# adc.net
KiCad netlist of a schematic drawn in Altium Designer
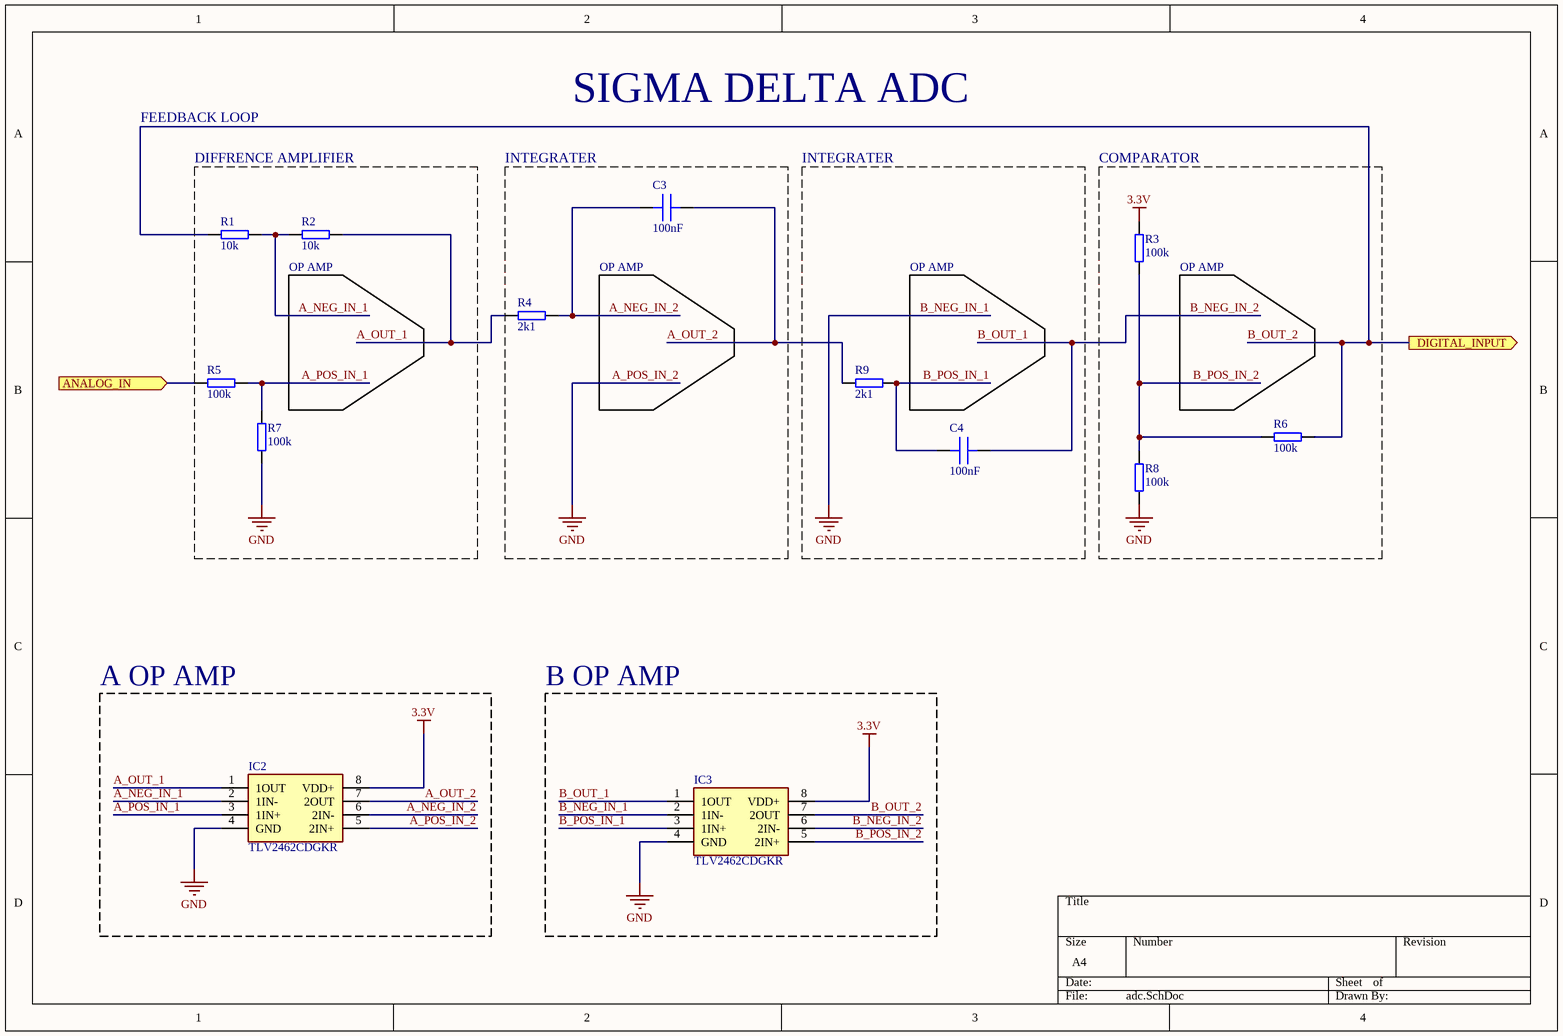
[diagram p0: adc.SchDoc]

(export (version "E")
  (design (tool "Eeschema 10.0.6"))
  (components
    (comp (ref "C3")
      (value "100nF")
      (footprint "C 0402")
      (description "MLCC Capacitor")
      (libsource (lib "sigma-delta-adc-uart") (part "Capacitor"))
    )
    (comp (ref "C4")
      (value "100nF")
      (footprint "C 0402")
      (description "MLCC Capacitor")
      (libsource (lib "sigma-delta-adc-uart") (part "Capacitor"))
    )
    (comp (ref "IC2")
      (value "TLV2462CDGKR")
      (footprint "SOP65P490X110-8N")
      (description "Integrated Circuit")
      (fields (field (name "MOUSER PART NUMBER") "595-TLV2462CDGKR"))
      (libsource (lib "sigma-delta-adc-uart") (part "TLV2462CDGKR"))
    )
    (comp (ref "IC3")
      (value "TLV2462CDGKR")
      (footprint "SOP65P490X110-8N")
      (description "Integrated Circuit")
      (fields (field (name "MOUSER PART NUMBER") "595-TLV2462CDGKR"))
      (libsource (lib "sigma-delta-adc-uart") (part "TLV2462CDGKR"))
    )
    (comp (ref "R1")
      (value "10k")
      (footprint "R 0402")
      (description "General pourpouse resistor")
      (libsource (lib "sigma-delta-adc-uart") (part "Resistor"))
    )
    (comp (ref "R2")
      (value "10k")
      (footprint "R 0402")
      (description "General pourpouse resistor")
      (libsource (lib "sigma-delta-adc-uart") (part "Resistor"))
    )
    (comp (ref "R3")
      (value "100k")
      (footprint "R 0402")
      (description "General pourpouse resistor")
      (libsource (lib "sigma-delta-adc-uart") (part "Resistor"))
    )
    (comp (ref "R4")
      (value "2k1")
      (footprint "R 0402")
      (description "General pourpouse resistor")
      (libsource (lib "sigma-delta-adc-uart") (part "Resistor"))
    )
    (comp (ref "R5")
      (value "100k")
      (footprint "R 0402")
      (description "General pourpouse resistor")
      (libsource (lib "sigma-delta-adc-uart") (part "Resistor"))
    )
    (comp (ref "R6")
      (value "100k")
      (footprint "R 0402")
      (description "General pourpouse resistor")
      (libsource (lib "sigma-delta-adc-uart") (part "Resistor"))
    )
    (comp (ref "R7")
      (value "100k")
      (footprint "R 0402")
      (description "General pourpouse resistor")
      (libsource (lib "sigma-delta-adc-uart") (part "Resistor"))
    )
    (comp (ref "R8")
      (value "100k")
      (footprint "R 0402")
      (description "General pourpouse resistor")
      (libsource (lib "sigma-delta-adc-uart") (part "Resistor"))
    )
    (comp (ref "R9")
      (value "2k1")
      (footprint "R 0402")
      (description "General pourpouse resistor")
      (libsource (lib "sigma-delta-adc-uart") (part "Resistor"))
    )
  )
  (nets
    (net (code "1") (name "/ANALOG_IN") (class "Default")
      (node (ref "R5") (pin "2") (pinfunction "2_2") (pintype "passive"))
    )
    (net (code "2") (name "/A_NEG_IN_1") (class "Default")
      (node (ref "IC2") (pin "2") (pinfunction "1IN-_2") (pintype "passive"))
      (node (ref "R1") (pin "1") (pinfunction "1_1") (pintype "passive"))
      (node (ref "R2") (pin "2") (pinfunction "2_2") (pintype "passive"))
    )
    (net (code "3") (name "/A_NEG_IN_2") (class "Default")
      (node (ref "C3") (pin "2") (pinfunction "2_2") (pintype "passive"))
      (node (ref "IC2") (pin "6") (pinfunction "2IN-_6") (pintype "passive"))
      (node (ref "R4") (pin "1") (pinfunction "1_1") (pintype "passive"))
    )
    (net (code "4") (name "/A_OUT_1") (class "Default")
      (node (ref "IC2") (pin "1") (pinfunction "1OUT_1") (pintype "passive"))
      (node (ref "R2") (pin "1") (pinfunction "1_1") (pintype "passive"))
      (node (ref "R4") (pin "2") (pinfunction "2_2") (pintype "passive"))
    )
    (net (code "5") (name "/A_OUT_2") (class "Default")
      (node (ref "C3") (pin "1") (pinfunction "1_1") (pintype "passive"))
      (node (ref "IC2") (pin "7") (pinfunction "2OUT_7") (pintype "passive"))
      (node (ref "R9") (pin "2") (pinfunction "2_2") (pintype "passive"))
    )
    (net (code "6") (name "/A_POS_IN_1") (class "Default")
      (node (ref "IC2") (pin "3") (pinfunction "1IN+_3") (pintype "passive"))
      (node (ref "R5") (pin "1") (pinfunction "1_1") (pintype "passive"))
      (node (ref "R7") (pin "1") (pinfunction "1_1") (pintype "passive"))
    )
    (net (code "7") (name "/B_NEG_IN_2") (class "Default")
      (node (ref "C4") (pin "1") (pinfunction "1_1") (pintype "passive"))
      (node (ref "IC3") (pin "1") (pinfunction "1OUT_1") (pintype "passive"))
      (node (ref "IC3") (pin "6") (pinfunction "2IN-_6") (pintype "passive"))
    )
    (net (code "8") (name "/B_OUT_2") (class "Default")
      (node (ref "IC3") (pin "7") (pinfunction "2OUT_7") (pintype "passive"))
      (node (ref "R1") (pin "2") (pinfunction "2_2") (pintype "passive"))
      (node (ref "R6") (pin "2") (pinfunction "2_2") (pintype "passive"))
    )
    (net (code "9") (name "/B_POS_IN_1") (class "Default")
      (node (ref "C4") (pin "2") (pinfunction "2_2") (pintype "passive"))
      (node (ref "IC3") (pin "3") (pinfunction "1IN+_3") (pintype "passive"))
      (node (ref "R9") (pin "1") (pinfunction "1_1") (pintype "passive"))
    )
    (net (code "10") (name "/B_POS_IN_2") (class "Default")
      (node (ref "IC3") (pin "5") (pinfunction "2IN+_5") (pintype "passive"))
      (node (ref "R3") (pin "2") (pinfunction "2_2") (pintype "passive"))
      (node (ref "R6") (pin "1") (pinfunction "1_1") (pintype "passive"))
      (node (ref "R8") (pin "1") (pinfunction "1_1") (pintype "passive"))
    )
    (net (code "11") (name "3.3V") (class "Default")
      (node (ref "IC2") (pin "8") (pinfunction "VDD+_8") (pintype "passive"))
      (node (ref "IC3") (pin "8") (pinfunction "VDD+_8") (pintype "passive"))
      (node (ref "R3") (pin "1") (pinfunction "1_1") (pintype "passive"))
    )
    (net (code "12") (name "GND") (class "Default")
      (node (ref "IC2") (pin "4") (pinfunction "GND_4") (pintype "passive"))
      (node (ref "IC2") (pin "5") (pinfunction "2IN+_5") (pintype "passive"))
      (node (ref "IC3") (pin "2") (pinfunction "1IN-_2") (pintype "passive"))
      (node (ref "IC3") (pin "4") (pinfunction "GND_4") (pintype "passive"))
      (node (ref "R7") (pin "2") (pinfunction "2_2") (pintype "passive"))
      (node (ref "R8") (pin "2") (pinfunction "2_2") (pintype "passive"))
    )
  )
)
